# Power.net
KiCad netlist of a schematic drawn in Altium Designer
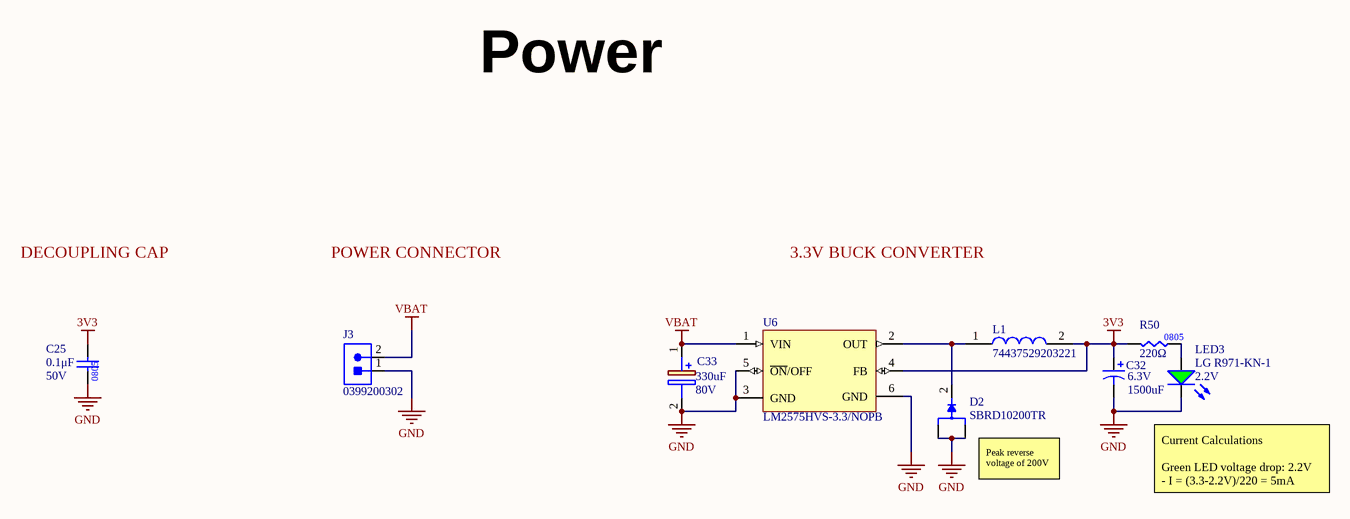
[diagram p0: Power.SchDoc]

(export (version "E")
  (design (tool "Eeschema 10.0.6"))
  (components
    (comp (ref "C25")
      (value "0.1μF")
      (footprint "CAP2012")
      (description "CAP CER 0.1UF 50V X7R 0805")
      (fields
        (field (name "VOLTAGE RATING") "50V")
        (field (name "LCSC PART #") "C49678")
        (field (name "Comment") "CAP_0.1uF_50V_0805")
      )
      (libsource (lib "UWRT_Schematic_Library_2020") (part "CAP_0.1uF_50V_0805"))
    )
    (comp (ref "C32")
      (value "PCJ0J152MCL1GS")
      (footprint "CAPAE1030X1080N")
      (fields (field (name "VOLTAGE") "6.3V") (field (name "CAPACITANCE") "1500uF"))
      (libsource (lib "UWRT_Schematic_Library_2020") (part "PCJ0J152MCL1GS"))
    )
    (comp (ref "C33")
      (value "EEV-FK1K331M")
      (footprint "EEEFK0J682AM")
      (description "Capacitor Polarised")
      (fields
        (field (name "MOUSER PART NUMBER") "667-EEV-FK1K331M")
        (field (name "CAPACITANCE") "330uF")
        (field (name "VOLTAGE") "80V")
      )
      (libsource (lib "UWRT_Schematic_Library_2020") (part "EEV-FK1K331M"))
    )
    (comp (ref "D2")
      (value "SBRD10200TR")
      (footprint "DPAK228P1005X240-4N")
      (description "SBRD10200 Series 200 V 10 A Surface Mount Schottky Rectifier - TO-252-3")
      (libsource (lib "UWRT_Schematic_Library_2020") (part "SBRD10200TR"))
    )
    (comp (ref "J3")
      (value "CONN_SCREW_TERM_115A")
      (footprint "MOLEX-0399200302")
      (description "CONN TERM BLOCK 2POS 15MM 1-8AWG")
      (fields (field (name "MANUFACTURER PART NUMBER 1") "0399200302"))
      (libsource (lib "UWRT_Schematic_Library_2020") (part "CONN_SCREW_TERM_115A"))
    )
    (comp (ref "L1")
      (value "74437529203221")
      (footprint "74437529203221")
      (description "Inductor")
      (fields (field (name "MOUSER PART NUMBER") "710-74437529203221"))
      (libsource (lib "UWRT_Schematic_Library_2020") (part "74437529203221"))
    )
    (comp (ref "LED3")
      (value "LED_GREEN")
      (footprint "LED_0805_GREEN")
      (description "LED GREEN DIFFUSED 0805 SMD")
      (fields
        (field (name "FORWARD VOLTAGE DROP") "2.2V")
        (field (name "MANUFACTURER PART NUMBER 1") "LG R971-KN-1")
      )
      (libsource (lib "UWRT_Schematic_Library_2020") (part "LED_GREEN"))
    )
    (comp (ref "R50")
      (value "220Ω")
      (footprint "RES0805")
      (description "RES 220 OHM 5% 1/2W 0805")
      (fields (field (name "LCSC PART #") "C17557") (field (name "Comment") "RES_220Ω_0805_5%"))
      (libsource (lib "UWRT_Schematic_Library_2020") (part "RES_220Ω_0805_5%"))
    )
    (comp (ref "U6")
      (value "LM2575HVS-3.3/NOPB")
      (footprint "VREG_TPS79625KTTR")
      (libsource (lib "UWRT_Schematic_Library_2020") (part "LM2575HVS-3.3/NOPB"))
    )
  )
  (nets
    (net (code "1") (name "3V3") (class "Default")
      (node (ref "C25") (pin "2") (pinfunction "2_2") (pintype "passive"))
      (node (ref "C32") (pin "1") (pinfunction "1_1") (pintype "passive"))
      (node (ref "L1") (pin "2") (pinfunction "2_2") (pintype "passive"))
      (node (ref "R50") (pin "1") (pinfunction "1_1") (pintype "passive"))
      (node (ref "U6") (pin "4") (pinfunction "FB_4") (pintype "bidirectional"))
    )
    (net (code "2") (name "GND") (class "Default")
      (node (ref "C25") (pin "1") (pinfunction "1_1") (pintype "passive"))
      (node (ref "C32") (pin "2") (pinfunction "2_2") (pintype "passive"))
      (node (ref "C33") (pin "2") (pinfunction "-_2") (pintype "passive"))
      (node (ref "D2") (pin "1") (pinfunction "1_1") (pintype "passive"))
      (node (ref "D2") (pin "3") (pinfunction "3_3") (pintype "passive"))
      (node (ref "J3") (pin "1") (pinfunction "1_1") (pintype "passive"))
      (node (ref "LED3") (pin "2") (pinfunction "K_2") (pintype "passive"))
      (node (ref "U6") (pin "3") (pinfunction "GND_3") (pintype "power_in"))
      (node (ref "U6") (pin "5") (pinfunction "~{ON}/OFF_5") (pintype "bidirectional"))
      (node (ref "U6") (pin "6") (pinfunction "GND_6") (pintype "power_in"))
    )
    (net (code "3") (name "Net-(LED3-A)") (class "Default")
      (node (ref "LED3") (pin "1") (pinfunction "A_1") (pintype "passive"))
      (node (ref "R50") (pin "2") (pinfunction "2_2") (pintype "passive"))
    )
    (net (code "4") (name "Net-(U6-OUT)") (class "Default")
      (node (ref "D2") (pin "2") (pinfunction "2_2") (pintype "passive"))
      (node (ref "L1") (pin "1") (pinfunction "1_1") (pintype "passive"))
      (node (ref "U6") (pin "2") (pinfunction "OUT_2") (pintype "output"))
    )
    (net (code "5") (name "VBAT") (class "Default")
      (node (ref "C33") (pin "1") (pinfunction "+_1") (pintype "passive"))
      (node (ref "J3") (pin "2") (pinfunction "2_2") (pintype "passive"))
      (node (ref "U6") (pin "1") (pinfunction "VIN_1") (pintype "input"))
    )
  )
)
